# untitled.net
KiCad netlist of a schematic drawn in EAGLE
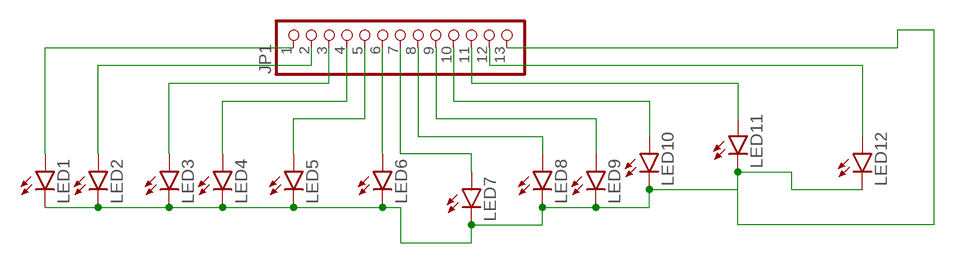
[diagram p0: schematic, sheet 1]

(export (version "E")
  (design (tool "Eeschema 10.0.6"))
  (components
    (comp (ref "JP1")
      (value "PINHD-1X13")
      (footprint "eagle-import:1X13")
      (libsource (lib "eagle-import") (part "PINHD-1X13"))
    )
    (comp (ref "LED1")
      (value "LED5MM")
      (footprint "eagle-import:LED5MM")
      (libsource (lib "eagle-import") (part "LED5MM"))
    )
    (comp (ref "LED2")
      (value "LED5MM")
      (footprint "eagle-import:LED5MM")
      (libsource (lib "eagle-import") (part "LED5MM"))
    )
    (comp (ref "LED3")
      (value "LED5MM")
      (footprint "eagle-import:LED5MM")
      (libsource (lib "eagle-import") (part "LED5MM"))
    )
    (comp (ref "LED4")
      (value "LED5MM")
      (footprint "eagle-import:LED5MM")
      (libsource (lib "eagle-import") (part "LED5MM"))
    )
    (comp (ref "LED5")
      (value "LED5MM")
      (footprint "eagle-import:LED5MM")
      (libsource (lib "eagle-import") (part "LED5MM"))
    )
    (comp (ref "LED6")
      (value "LED5MM")
      (footprint "eagle-import:LED5MM")
      (libsource (lib "eagle-import") (part "LED5MM"))
    )
    (comp (ref "LED7")
      (value "LED5MM")
      (footprint "eagle-import:LED5MM")
      (libsource (lib "eagle-import") (part "LED5MM"))
    )
    (comp (ref "LED8")
      (value "LED5MM")
      (footprint "eagle-import:LED5MM")
      (libsource (lib "eagle-import") (part "LED5MM"))
    )
    (comp (ref "LED9")
      (value "LED5MM")
      (footprint "eagle-import:LED5MM")
      (libsource (lib "eagle-import") (part "LED5MM"))
    )
    (comp (ref "LED10")
      (value "LED5MM")
      (footprint "eagle-import:LED5MM")
      (libsource (lib "eagle-import") (part "LED5MM"))
    )
    (comp (ref "LED11")
      (value "LED5MM")
      (footprint "eagle-import:LED5MM")
      (libsource (lib "eagle-import") (part "LED5MM"))
    )
    (comp (ref "LED12")
      (value "LED5MM")
      (footprint "eagle-import:LED5MM")
      (libsource (lib "eagle-import") (part "LED5MM"))
    )
  )
  (nets
    (net (code "1") (name "Net-(JP1-Pad1)") (class "Default")
      (node (ref "JP1") (pin "1") (pinfunction "1_1") (pintype "passive"))
      (node (ref "LED1") (pin "A") (pinfunction "A_A") (pintype "passive"))
    )
    (net (code "2") (name "Net-(JP1-Pad2)") (class "Default")
      (node (ref "JP1") (pin "2") (pinfunction "2_2") (pintype "passive"))
      (node (ref "LED2") (pin "A") (pinfunction "A_A") (pintype "passive"))
    )
    (net (code "3") (name "Net-(JP1-Pad3)") (class "Default")
      (node (ref "JP1") (pin "3") (pinfunction "3_3") (pintype "passive"))
      (node (ref "LED3") (pin "A") (pinfunction "A_A") (pintype "passive"))
    )
    (net (code "4") (name "Net-(JP1-Pad4)") (class "Default")
      (node (ref "JP1") (pin "4") (pinfunction "4_4") (pintype "passive"))
      (node (ref "LED4") (pin "A") (pinfunction "A_A") (pintype "passive"))
    )
    (net (code "5") (name "Net-(JP1-Pad5)") (class "Default")
      (node (ref "JP1") (pin "5") (pinfunction "5_5") (pintype "passive"))
      (node (ref "LED5") (pin "A") (pinfunction "A_A") (pintype "passive"))
    )
    (net (code "6") (name "Net-(JP1-Pad6)") (class "Default")
      (node (ref "JP1") (pin "6") (pinfunction "6_6") (pintype "passive"))
      (node (ref "LED6") (pin "A") (pinfunction "A_A") (pintype "passive"))
    )
    (net (code "7") (name "Net-(JP1-Pad7)") (class "Default")
      (node (ref "JP1") (pin "7") (pinfunction "7_7") (pintype "passive"))
      (node (ref "LED7") (pin "A") (pinfunction "A_A") (pintype "passive"))
    )
    (net (code "8") (name "Net-(JP1-Pad8)") (class "Default")
      (node (ref "JP1") (pin "8") (pinfunction "8_8") (pintype "passive"))
      (node (ref "LED8") (pin "A") (pinfunction "A_A") (pintype "passive"))
    )
    (net (code "9") (name "Net-(JP1-Pad9)") (class "Default")
      (node (ref "JP1") (pin "9") (pinfunction "9_9") (pintype "passive"))
      (node (ref "LED9") (pin "A") (pinfunction "A_A") (pintype "passive"))
    )
    (net (code "10") (name "Net-(JP1-Pad10)") (class "Default")
      (node (ref "JP1") (pin "10") (pinfunction "10_10") (pintype "passive"))
      (node (ref "LED10") (pin "A") (pinfunction "A_A") (pintype "passive"))
    )
    (net (code "11") (name "Net-(JP1-Pad11)") (class "Default")
      (node (ref "JP1") (pin "11") (pinfunction "11_11") (pintype "passive"))
      (node (ref "LED11") (pin "A") (pinfunction "A_A") (pintype "passive"))
    )
    (net (code "12") (name "Net-(JP1-Pad12)") (class "Default")
      (node (ref "JP1") (pin "12") (pinfunction "12_12") (pintype "passive"))
      (node (ref "LED12") (pin "A") (pinfunction "A_A") (pintype "passive"))
    )
    (net (code "13") (name "Net-(LED1-C)") (class "Default")
      (node (ref "JP1") (pin "13") (pinfunction "13_13") (pintype "passive"))
      (node (ref "LED1") (pin "K") (pinfunction "C_K") (pintype "passive"))
      (node (ref "LED10") (pin "K") (pinfunction "C_K") (pintype "passive"))
      (node (ref "LED11") (pin "K") (pinfunction "C_K") (pintype "passive"))
      (node (ref "LED12") (pin "K") (pinfunction "C_K") (pintype "passive"))
      (node (ref "LED2") (pin "K") (pinfunction "C_K") (pintype "passive"))
      (node (ref "LED3") (pin "K") (pinfunction "C_K") (pintype "passive"))
      (node (ref "LED4") (pin "K") (pinfunction "C_K") (pintype "passive"))
      (node (ref "LED5") (pin "K") (pinfunction "C_K") (pintype "passive"))
      (node (ref "LED6") (pin "K") (pinfunction "C_K") (pintype "passive"))
      (node (ref "LED7") (pin "K") (pinfunction "C_K") (pintype "passive"))
      (node (ref "LED8") (pin "K") (pinfunction "C_K") (pintype "passive"))
      (node (ref "LED9") (pin "K") (pinfunction "C_K") (pintype "passive"))
    )
  )
)
